# hextokWings03h.net
KiCad netlist of a schematic drawn in EAGLE
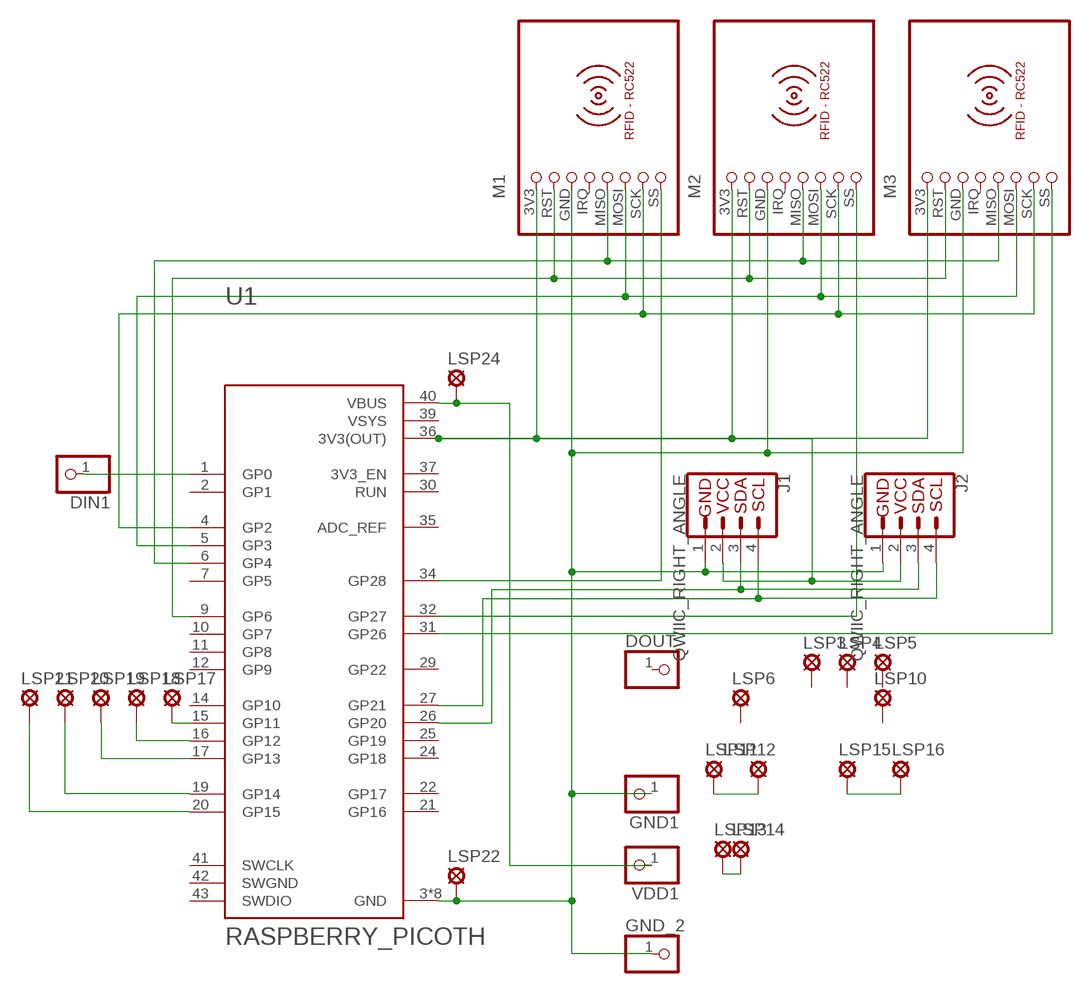
[diagram p0: schematic, sheet 1]

(export (version "E")
  (design (tool "Eeschema 10.0.6"))
  (components
    (comp (ref "DIN1")
      (value "PINHD-1X1CB")
      (footprint "eagle-import:1X01-CLEANBIG")
      (libsource (lib "eagle-import") (part "PINHD-1X1CB"))
    )
    (comp (ref "DOUT")
      (value "PINHD-1X1CB")
      (footprint "eagle-import:1X01-CLEANBIG")
      (libsource (lib "eagle-import") (part "PINHD-1X1CB"))
    )
    (comp (ref "GND1")
      (value "PINHD-1X1CB")
      (footprint "eagle-import:1X01-CLEANBIG")
      (libsource (lib "eagle-import") (part "PINHD-1X1CB"))
    )
    (comp (ref "GND_2")
      (value "PINHD-1X1CB")
      (footprint "eagle-import:1X01-CLEANBIG")
      (libsource (lib "eagle-import") (part "PINHD-1X1CB"))
    )
    (comp (ref "J1")
      (value "QWIIC_RIGHT_ANGLE")
      (footprint "eagle-import:JST04_1MM_RA")
      (libsource (lib "eagle-import") (part "QWIIC_CONNECTORJS-1MM"))
    )
    (comp (ref "J2")
      (value "QWIIC_RIGHT_ANGLE")
      (footprint "eagle-import:JST04_1MM_RA")
      (libsource (lib "eagle-import") (part "QWIIC_CONNECTORJS-1MM"))
    )
    (comp (ref "LSP3")
      (value "LSP10")
      (footprint "eagle-import:LSP10")
      (libsource (lib "eagle-import") (part "LSP10"))
    )
    (comp (ref "LSP4")
      (value "LSP10")
      (footprint "eagle-import:LSP10")
      (libsource (lib "eagle-import") (part "LSP10"))
    )
    (comp (ref "LSP5")
      (value "LSP10")
      (footprint "eagle-import:LSP10")
      (libsource (lib "eagle-import") (part "LSP10"))
    )
    (comp (ref "LSP6")
      (value "LSP10")
      (footprint "eagle-import:LSP10")
      (libsource (lib "eagle-import") (part "LSP10"))
    )
    (comp (ref "LSP10")
      (value "LSP10")
      (footprint "eagle-import:LSP10")
      (libsource (lib "eagle-import") (part "LSP10"))
    )
    (comp (ref "LSP11")
      (value "LSP10")
      (footprint "eagle-import:LSP10")
      (libsource (lib "eagle-import") (part "LSP10"))
    )
    (comp (ref "LSP12")
      (value "LSP10")
      (footprint "eagle-import:LSP10")
      (libsource (lib "eagle-import") (part "LSP10"))
    )
    (comp (ref "LSP13")
      (value "LSP10")
      (footprint "eagle-import:LSP10")
      (libsource (lib "eagle-import") (part "LSP10"))
    )
    (comp (ref "LSP14")
      (value "LSP10")
      (footprint "eagle-import:LSP10")
      (libsource (lib "eagle-import") (part "LSP10"))
    )
    (comp (ref "LSP15")
      (value "LSP10")
      (footprint "eagle-import:LSP10")
      (libsource (lib "eagle-import") (part "LSP10"))
    )
    (comp (ref "LSP16")
      (value "LSP10")
      (footprint "eagle-import:LSP10")
      (libsource (lib "eagle-import") (part "LSP10"))
    )
    (comp (ref "LSP17")
      (value "LSP10")
      (footprint "eagle-import:LSP10")
      (libsource (lib "eagle-import") (part "LSP10"))
    )
    (comp (ref "LSP18")
      (value "LSP10")
      (footprint "eagle-import:LSP10")
      (libsource (lib "eagle-import") (part "LSP10"))
    )
    (comp (ref "LSP19")
      (value "LSP10")
      (footprint "eagle-import:LSP10")
      (libsource (lib "eagle-import") (part "LSP10"))
    )
    (comp (ref "LSP20")
      (value "LSP10")
      (footprint "eagle-import:LSP10")
      (libsource (lib "eagle-import") (part "LSP10"))
    )
    (comp (ref "LSP21")
      (value "LSP10")
      (footprint "eagle-import:LSP10")
      (libsource (lib "eagle-import") (part "LSP10"))
    )
    (comp (ref "LSP22")
      (value "LSP10")
      (footprint "eagle-import:LSP10")
      (libsource (lib "eagle-import") (part "LSP10"))
    )
    (comp (ref "LSP24")
      (value "LSP10")
      (footprint "eagle-import:LSP10")
      (libsource (lib "eagle-import") (part "LSP10"))
    )
    (comp (ref "M1")
      (value "RFID-RC522")
      (footprint "eagle-import:RFID-RC522")
      (libsource (lib "eagle-import") (part "RFID-RC522"))
    )
    (comp (ref "M2")
      (value "RFID-RC522")
      (footprint "eagle-import:RFID-RC522")
      (libsource (lib "eagle-import") (part "RFID-RC522"))
    )
    (comp (ref "M3")
      (value "RFID-RC522")
      (footprint "eagle-import:RFID-RC522")
      (libsource (lib "eagle-import") (part "RFID-RC522"))
    )
    (comp (ref "U1")
      (value "RASPBERRY_PICOTH")
      (footprint "eagle-import:PICO-PKG-TH")
      (libsource (lib "eagle-import") (part "RASPBERRY_PICOTH"))
    )
    (comp (ref "VDD1")
      (value "PINHD-1X1CB")
      (footprint "eagle-import:1X01-CLEANBIG")
      (libsource (lib "eagle-import") (part "PINHD-1X1CB"))
    )
  )
  (nets
    (net (code "1") (name "/SWGND") (class "Default")
      (node (ref "U1") (pin "42") (pinfunction "SWGND_42") (pintype "power_in"))
    )
    (net (code "2") (name "/VSYS") (class "Default")
      (node (ref "U1") (pin "39") (pinfunction "VSYS_39") (pintype "power_in"))
    )
    (net (code "3") (name "Net-(LSP11-PadMP)") (class "Default")
      (node (ref "LSP11") (pin "MP") (pinfunction "MP_MP") (pintype "passive"))
      (node (ref "LSP12") (pin "MP") (pinfunction "MP_MP") (pintype "passive"))
    )
    (net (code "4") (name "Net-(LSP13-PadMP)") (class "Default")
      (node (ref "LSP13") (pin "MP") (pinfunction "MP_MP") (pintype "passive"))
      (node (ref "LSP14") (pin "MP") (pinfunction "MP_MP") (pintype "passive"))
    )
    (net (code "5") (name "Net-(LSP15-PadMP)") (class "Default")
      (node (ref "LSP15") (pin "MP") (pinfunction "MP_MP") (pintype "passive"))
      (node (ref "LSP16") (pin "MP") (pinfunction "MP_MP") (pintype "passive"))
    )
    (net (code "6") (name "Net-(M1-1)") (class "Default")
      (node (ref "J1") (pin "2") (pinfunction "2_2") (pintype "power_in"))
      (node (ref "J2") (pin "2") (pinfunction "2_2") (pintype "power_in"))
      (node (ref "M1") (pin "3V3") (pinfunction "1_3V3") (pintype "passive"))
      (node (ref "M2") (pin "3V3") (pinfunction "1_3V3") (pintype "passive"))
      (node (ref "M3") (pin "3V3") (pinfunction "1_3V3") (pintype "passive"))
      (node (ref "U1") (pin "36") (pinfunction "3V3(OUT)_36") (pintype "power_in"))
    )
    (net (code "7") (name "Net-(M1-2)") (class "Default")
      (node (ref "M1") (pin "RST") (pinfunction "2_RST") (pintype "passive"))
      (node (ref "M2") (pin "RST") (pinfunction "2_RST") (pintype "passive"))
      (node (ref "M3") (pin "RST") (pinfunction "2_RST") (pintype "passive"))
      (node (ref "U1") (pin "9") (pinfunction "GP6_9") (pintype "bidirectional"))
    )
    (net (code "8") (name "Net-(M1-3)") (class "Default")
      (node (ref "GND1") (pin "1") (pinfunction "1_1") (pintype "passive"))
      (node (ref "GND_2") (pin "1") (pinfunction "1_1") (pintype "passive"))
      (node (ref "J1") (pin "1") (pinfunction "1_1") (pintype "power_in"))
      (node (ref "J2") (pin "1") (pinfunction "1_1") (pintype "power_in"))
      (node (ref "LSP22") (pin "MP") (pinfunction "MP_MP") (pintype "passive"))
      (node (ref "M1") (pin "GND") (pinfunction "3_GND") (pintype "passive"))
      (node (ref "M2") (pin "GND") (pinfunction "3_GND") (pintype "passive"))
      (node (ref "M3") (pin "GND") (pinfunction "3_GND") (pintype "passive"))
      (node (ref "U1") (pin "13") (pinfunction "GND_13") (pintype "power_in"))
      (node (ref "U1") (pin "18") (pinfunction "GND_18") (pintype "power_in"))
      (node (ref "U1") (pin "23") (pinfunction "GND_23") (pintype "power_in"))
      (node (ref "U1") (pin "28") (pinfunction "GND_28") (pintype "power_in"))
      (node (ref "U1") (pin "3") (pinfunction "GND_3") (pintype "power_in"))
      (node (ref "U1") (pin "33") (pinfunction "GND_33") (pintype "power_in"))
      (node (ref "U1") (pin "38") (pinfunction "GND_38") (pintype "power_in"))
      (node (ref "U1") (pin "8") (pinfunction "GND_8") (pintype "power_in"))
    )
    (net (code "9") (name "Net-(M1-5)") (class "Default")
      (node (ref "M1") (pin "MISO") (pinfunction "5_MISO") (pintype "passive"))
      (node (ref "M2") (pin "MISO") (pinfunction "5_MISO") (pintype "passive"))
      (node (ref "M3") (pin "MISO") (pinfunction "5_MISO") (pintype "passive"))
      (node (ref "U1") (pin "6") (pinfunction "GP4_6") (pintype "bidirectional"))
    )
    (net (code "10") (name "Net-(M1-6)") (class "Default")
      (node (ref "M1") (pin "MOSI") (pinfunction "6_MOSI") (pintype "passive"))
      (node (ref "M2") (pin "MOSI") (pinfunction "6_MOSI") (pintype "passive"))
      (node (ref "M3") (pin "MOSI") (pinfunction "6_MOSI") (pintype "passive"))
      (node (ref "U1") (pin "5") (pinfunction "GP3_5") (pintype "bidirectional"))
    )
    (net (code "11") (name "Net-(M1-7)") (class "Default")
      (node (ref "M1") (pin "SCK") (pinfunction "7_SCK") (pintype "passive"))
      (node (ref "M2") (pin "SCK") (pinfunction "7_SCK") (pintype "passive"))
      (node (ref "M3") (pin "SCK") (pinfunction "7_SCK") (pintype "passive"))
      (node (ref "U1") (pin "4") (pinfunction "GP2_4") (pintype "bidirectional"))
    )
    (net (code "12") (name "Net-(M1-8)") (class "Default")
      (node (ref "M1") (pin "SS") (pinfunction "8_SS") (pintype "passive"))
      (node (ref "U1") (pin "34") (pinfunction "GP28_34") (pintype "bidirectional"))
    )
    (net (code "13") (name "Net-(M2-8)") (class "Default")
      (node (ref "M2") (pin "SS") (pinfunction "8_SS") (pintype "passive"))
      (node (ref "U1") (pin "32") (pinfunction "GP27_32") (pintype "bidirectional"))
    )
    (net (code "14") (name "Net-(M3-8)") (class "Default")
      (node (ref "M3") (pin "SS") (pinfunction "8_SS") (pintype "passive"))
      (node (ref "U1") (pin "31") (pinfunction "GP26_31") (pintype "bidirectional"))
    )
    (net (code "15") (name "Net-(U1-GP0)") (class "Default")
      (node (ref "DIN1") (pin "1") (pinfunction "1_1") (pintype "passive"))
      (node (ref "U1") (pin "1") (pinfunction "GP0_1") (pintype "bidirectional"))
    )
    (net (code "16") (name "Net-(U1-GP11)") (class "Default")
      (node (ref "LSP17") (pin "MP") (pinfunction "MP_MP") (pintype "passive"))
      (node (ref "U1") (pin "15") (pinfunction "GP11_15") (pintype "bidirectional"))
    )
    (net (code "17") (name "Net-(U1-GP12)") (class "Default")
      (node (ref "LSP18") (pin "MP") (pinfunction "MP_MP") (pintype "passive"))
      (node (ref "U1") (pin "16") (pinfunction "GP12_16") (pintype "bidirectional"))
    )
    (net (code "18") (name "Net-(U1-GP13)") (class "Default")
      (node (ref "LSP19") (pin "MP") (pinfunction "MP_MP") (pintype "passive"))
      (node (ref "U1") (pin "17") (pinfunction "GP13_17") (pintype "bidirectional"))
    )
    (net (code "19") (name "Net-(U1-GP14)") (class "Default")
      (node (ref "LSP20") (pin "MP") (pinfunction "MP_MP") (pintype "passive"))
      (node (ref "U1") (pin "19") (pinfunction "GP14_19") (pintype "bidirectional"))
    )
    (net (code "20") (name "Net-(U1-GP15)") (class "Default")
      (node (ref "LSP21") (pin "MP") (pinfunction "MP_MP") (pintype "passive"))
      (node (ref "U1") (pin "20") (pinfunction "GP15_20") (pintype "bidirectional"))
    )
    (net (code "21") (name "Net-(U1-GP20)") (class "Default")
      (node (ref "J1") (pin "3") (pinfunction "3_3") (pintype "passive"))
      (node (ref "J2") (pin "3") (pinfunction "3_3") (pintype "passive"))
      (node (ref "U1") (pin "26") (pinfunction "GP20_26") (pintype "bidirectional"))
    )
    (net (code "22") (name "Net-(U1-GP21)") (class "Default")
      (node (ref "J1") (pin "4") (pinfunction "4_4") (pintype "passive"))
      (node (ref "J2") (pin "4") (pinfunction "4_4") (pintype "passive"))
      (node (ref "U1") (pin "27") (pinfunction "GP21_27") (pintype "bidirectional"))
    )
    (net (code "23") (name "Net-(U1-VBUS)") (class "Default")
      (node (ref "LSP24") (pin "MP") (pinfunction "MP_MP") (pintype "passive"))
      (node (ref "U1") (pin "40") (pinfunction "VBUS_40") (pintype "power_in"))
      (node (ref "VDD1") (pin "1") (pinfunction "1_1") (pintype "passive"))
    )
    (net (code "24") (name "unconnected-(DOUT-Pad1)") (class "Default")
      (node (ref "DOUT") (pin "1") (pinfunction "1_1") (pintype "passive"))
    )
    (net (code "25") (name "unconnected-(LSP3-PadMP)") (class "Default")
      (node (ref "LSP3") (pin "MP") (pinfunction "MP_MP") (pintype "passive"))
    )
    (net (code "26") (name "unconnected-(LSP4-PadMP)") (class "Default")
      (node (ref "LSP4") (pin "MP") (pinfunction "MP_MP") (pintype "passive"))
    )
    (net (code "27") (name "unconnected-(LSP5-PadMP)") (class "Default")
      (node (ref "LSP5") (pin "MP") (pinfunction "MP_MP") (pintype "passive"))
    )
    (net (code "28") (name "unconnected-(LSP6-PadMP)") (class "Default")
      (node (ref "LSP6") (pin "MP") (pinfunction "MP_MP") (pintype "passive"))
    )
    (net (code "29") (name "unconnected-(LSP10-PadMP)") (class "Default")
      (node (ref "LSP10") (pin "MP") (pinfunction "MP_MP") (pintype "passive"))
    )
    (net (code "30") (name "unconnected-(M1-4-PadIRQ)") (class "Default")
      (node (ref "M1") (pin "IRQ") (pinfunction "4_IRQ") (pintype "passive"))
    )
    (net (code "31") (name "unconnected-(M2-4-PadIRQ)") (class "Default")
      (node (ref "M2") (pin "IRQ") (pinfunction "4_IRQ") (pintype "passive"))
    )
    (net (code "32") (name "unconnected-(M3-4-PadIRQ)") (class "Default")
      (node (ref "M3") (pin "IRQ") (pinfunction "4_IRQ") (pintype "passive"))
    )
    (net (code "33") (name "unconnected-(U1-3V3_EN-Pad37)") (class "Default")
      (node (ref "U1") (pin "37") (pinfunction "3V3_EN_37") (pintype "input"))
    )
    (net (code "34") (name "unconnected-(U1-ADC_REF-Pad35)") (class "Default")
      (node (ref "U1") (pin "35") (pinfunction "ADC_REF_35") (pintype "input"))
    )
    (net (code "35") (name "unconnected-(U1-GP1-Pad2)") (class "Default")
      (node (ref "U1") (pin "2") (pinfunction "GP1_2") (pintype "bidirectional"))
    )
    (net (code "36") (name "unconnected-(U1-GP5-Pad7)") (class "Default")
      (node (ref "U1") (pin "7") (pinfunction "GP5_7") (pintype "bidirectional"))
    )
    (net (code "37") (name "unconnected-(U1-GP7-Pad10)") (class "Default")
      (node (ref "U1") (pin "10") (pinfunction "GP7_10") (pintype "bidirectional"))
    )
    (net (code "38") (name "unconnected-(U1-GP8-Pad11)") (class "Default")
      (node (ref "U1") (pin "11") (pinfunction "GP8_11") (pintype "bidirectional"))
    )
    (net (code "39") (name "unconnected-(U1-GP9-Pad12)") (class "Default")
      (node (ref "U1") (pin "12") (pinfunction "GP9_12") (pintype "bidirectional"))
    )
    (net (code "40") (name "unconnected-(U1-GP10-Pad14)") (class "Default")
      (node (ref "U1") (pin "14") (pinfunction "GP10_14") (pintype "bidirectional"))
    )
    (net (code "41") (name "unconnected-(U1-GP16-Pad21)") (class "Default")
      (node (ref "U1") (pin "21") (pinfunction "GP16_21") (pintype "bidirectional"))
    )
    (net (code "42") (name "unconnected-(U1-GP17-Pad22)") (class "Default")
      (node (ref "U1") (pin "22") (pinfunction "GP17_22") (pintype "bidirectional"))
    )
    (net (code "43") (name "unconnected-(U1-GP18-Pad24)") (class "Default")
      (node (ref "U1") (pin "24") (pinfunction "GP18_24") (pintype "bidirectional"))
    )
    (net (code "44") (name "unconnected-(U1-GP19-Pad25)") (class "Default")
      (node (ref "U1") (pin "25") (pinfunction "GP19_25") (pintype "bidirectional"))
    )
    (net (code "45") (name "unconnected-(U1-GP22-Pad29)") (class "Default")
      (node (ref "U1") (pin "29") (pinfunction "GP22_29") (pintype "bidirectional"))
    )
    (net (code "46") (name "unconnected-(U1-RUN-Pad30)") (class "Default")
      (node (ref "U1") (pin "30") (pinfunction "RUN_30") (pintype "input"))
    )
    (net (code "47") (name "unconnected-(U1-SWCLK-Pad41)") (class "Default")
      (node (ref "U1") (pin "41") (pinfunction "SWCLK_41") (pintype "input"))
    )
    (net (code "48") (name "unconnected-(U1-SWDIO-Pad43)") (class "Default")
      (node (ref "U1") (pin "43") (pinfunction "SWDIO_43") (pintype "bidirectional"))
    )
  )
)
